# DM2097_Connector_B.net
KiCad netlist of a schematic drawn in Altium Designer
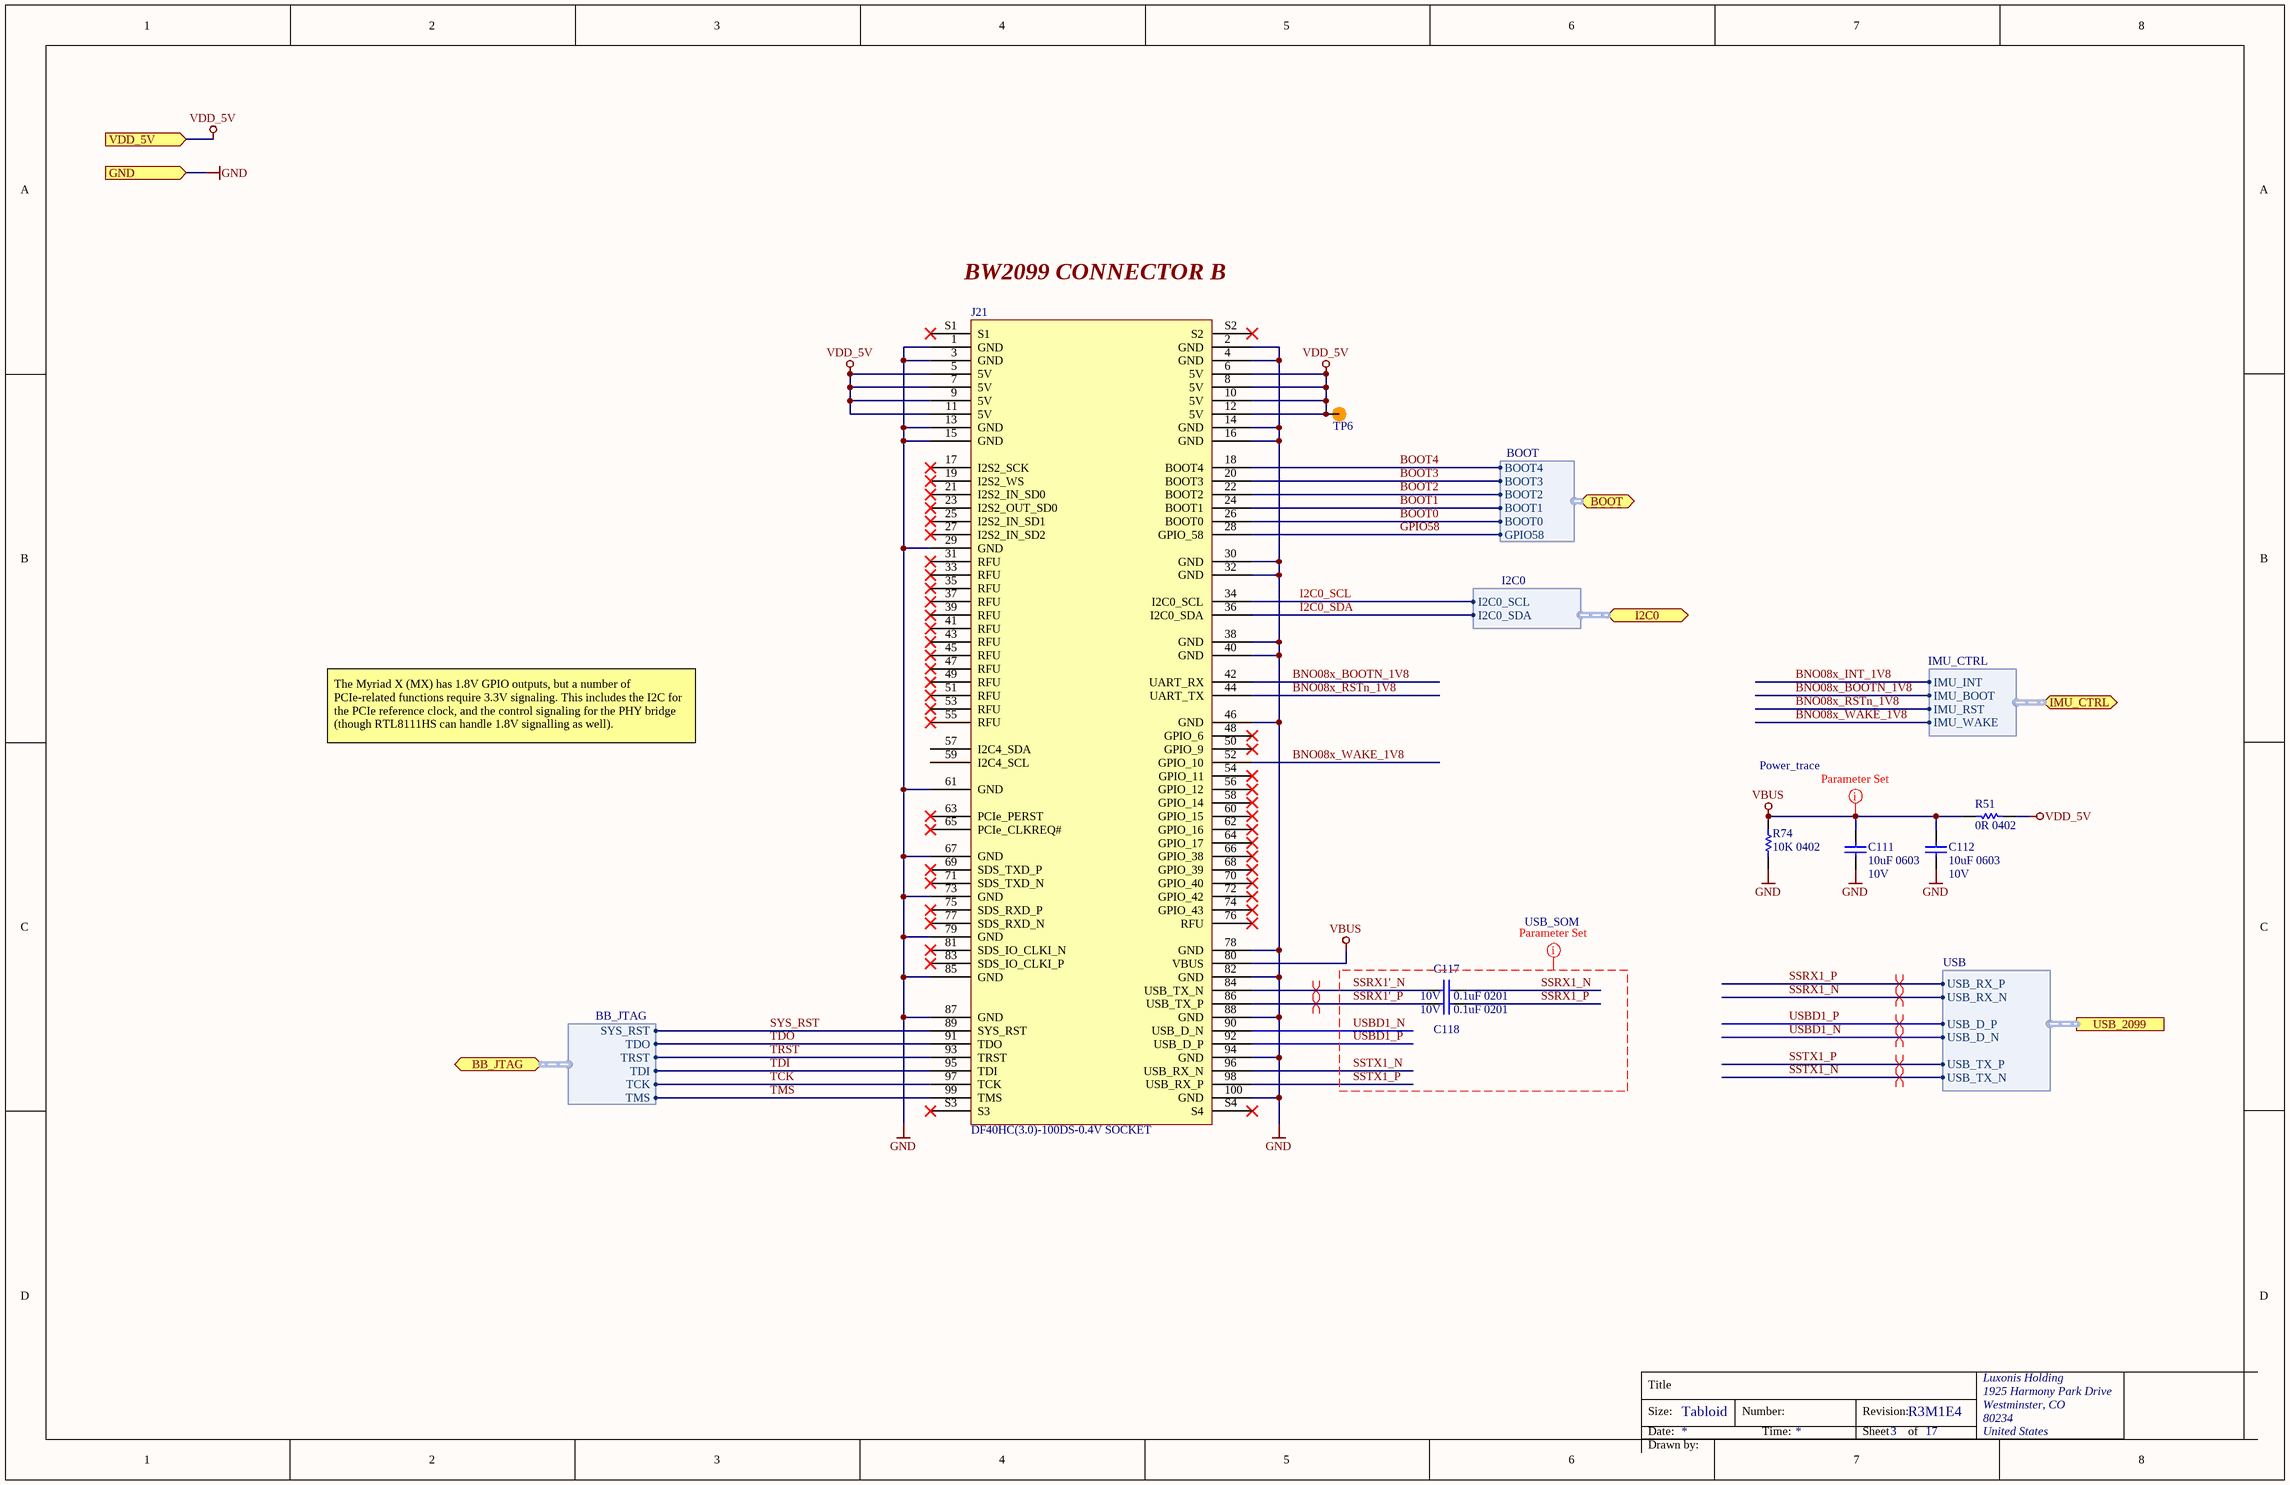
[diagram p0: DM2097_Connector_B.SchDoc]

(export (version "E")
  (design (tool "Eeschema 10.0.6"))
  (components
    (comp (ref "C111")
      (value "10uF 0603")
      (footprint "CAP_Altium_Vault_Generic:CAPC0603(1608)100_N")
      (description "CAP CER 10UF 10V X5R 0603 20%")
      (fields (field (name "TOLERANCE") "20%") (field (name "VOLTAGE RATING") "10V"))
      (libsource (lib "LuxonisMaster") (part "GRM188R61A106ME69D"))
    )
    (comp (ref "C112")
      (value "10uF 0603")
      (footprint "CAP_Altium_Vault_Generic:CAPC0603(1608)100_N")
      (description "CAP CER 10UF 10V X5R 0603 20%")
      (fields (field (name "TOLERANCE") "20%") (field (name "VOLTAGE RATING") "10V"))
      (libsource (lib "LuxonisMaster") (part "GRM188R61A106ME69D"))
    )
    (comp (ref "C117")
      (value "0.1uF 0201")
      (footprint "CAP_Altium_Vault_Generic:CAPC0201(0603)33_L")
      (description "CAP CER 0.1UF 10V X5R 0201")
      (fields (field (name "TOLERANCE") "10%") (field (name "VOLTAGE") "10V"))
      (libsource (lib "LuxonisMaster") (part "GRM033R61A104KE15D"))
    )
    (comp (ref "C118")
      (value "0.1uF 0201")
      (footprint "CAP_Altium_Vault_Generic:CAPC0201(0603)33_L")
      (description "CAP CER 0.1UF 10V X5R 0201")
      (fields (field (name "TOLERANCE") "10%") (field (name "VOLTAGE") "10V"))
      (libsource (lib "LuxonisMaster") (part "GRM033R61A104KE15D"))
    )
    (comp (ref "J21")
      (value "DF40HC(3.0)-100DS-0.4V SOCKET")
      (footprint "DF40HC-3.0-100DS-0.4V_minpad")
      (description "Conn Board to Board RCP 100 POS 0.4mm Solder ST SMD T/R")
      (libsource (lib "LuxonisMaster_OPAL") (part "BW2099_SCKT_Conn_B"))
    )
    (comp (ref "R51")
      (value "0R 0402")
      (footprint "RES_Altium_Vault_Generic:RESC0402(1005)_N")
      (description "RES SMD 0 OHM JUMPER 1/16W 0402")
      (fields (field (name "TOLERANCE") "5%"))
      (libsource (lib "LuxonisMaster") (part "CRCW04020000Z0ED"))
    )
    (comp (ref "R74")
      (value "10K 0402")
      (footprint "RES_Altium_Vault_Generic:RESC0402(1005)_N")
      (fields (field (name "TOLERANCE") "1%"))
      (libsource (lib "LuxonisMaster") (part "RC0402FR-1310KL"))
    )
    (comp (ref "TP6")
      (value "TP100_200_NS")
      (footprint "LuxonisMaster:TP100_200_NS")
      (libsource (lib "LuxonisMaster") (part "TEST_POINT"))
    )
  )
  (nets
    (net (code "6") (name "/BNO08x_BOOTN_1V8") (class "Default")
      (node (ref "J21") (pin "42") (pinfunction "UART_RX_42") (pintype "passive"))
    )
    (net (code "8") (name "/BNO08x_RSTn_1V8") (class "Default")
      (node (ref "J21") (pin "44") (pinfunction "UART_TX_44") (pintype "passive"))
    )
    (net (code "9") (name "/BNO08x_WAKE_1V8") (class "Default")
      (node (ref "J21") (pin "52") (pinfunction "GPIO_10_52") (pintype "passive"))
    )
    (net (code "10") (name "/BOOT0") (class "Default")
      (node (ref "J21") (pin "26") (pinfunction "BOOT0_26") (pintype "passive"))
    )
    (net (code "11") (name "/BOOT1") (class "Default")
      (node (ref "J21") (pin "24") (pinfunction "BOOT1_24") (pintype "passive"))
    )
    (net (code "12") (name "/BOOT2") (class "Default")
      (node (ref "J21") (pin "22") (pinfunction "BOOT2_22") (pintype "passive"))
    )
    (net (code "13") (name "/BOOT3") (class "Default")
      (node (ref "J21") (pin "20") (pinfunction "BOOT3_20") (pintype "passive"))
    )
    (net (code "14") (name "/BOOT4") (class "Default")
      (node (ref "J21") (pin "18") (pinfunction "BOOT4_18") (pintype "passive"))
    )
    (net (code "15") (name "/GPIO58") (class "Default")
      (node (ref "J21") (pin "28") (pinfunction "GPIO_58_28") (pintype "passive"))
    )
    (net (code "16") (name "/I2C0_SCL") (class "Default")
      (node (ref "J21") (pin "34") (pinfunction "I2C0_SCL_34") (pintype "passive"))
    )
    (net (code "17") (name "/I2C0_SDA") (class "Default")
      (node (ref "J21") (pin "36") (pinfunction "I2C0_SDA_36") (pintype "passive"))
    )
    (net (code "18") (name "/SSRX1'_N") (class "Default")
      (node (ref "C117") (pin "1") (pinfunction "1_1") (pintype "passive"))
      (node (ref "J21") (pin "84") (pinfunction "USB_TX_N_84") (pintype "passive"))
    )
    (net (code "19") (name "/SSRX1'_P") (class "Default")
      (node (ref "C118") (pin "1") (pinfunction "1_1") (pintype "passive"))
      (node (ref "J21") (pin "86") (pinfunction "USB_TX_P_86") (pintype "passive"))
    )
    (net (code "20") (name "/SSRX1_N") (class "Default")
      (node (ref "C117") (pin "2") (pinfunction "2_2") (pintype "passive"))
    )
    (net (code "21") (name "/SSRX1_P") (class "Default")
      (node (ref "C118") (pin "2") (pinfunction "2_2") (pintype "passive"))
    )
    (net (code "22") (name "/SSTX1_N") (class "Default")
      (node (ref "J21") (pin "96") (pinfunction "USB_RX_N_96") (pintype "passive"))
    )
    (net (code "23") (name "/SSTX1_P") (class "Default")
      (node (ref "J21") (pin "98") (pinfunction "USB_RX_P_98") (pintype "passive"))
    )
    (net (code "24") (name "/SYS_RST") (class "Default")
      (node (ref "J21") (pin "89") (pinfunction "SYS_RST_89") (pintype "passive"))
    )
    (net (code "25") (name "/TCK") (class "Default")
      (node (ref "J21") (pin "97") (pinfunction "TCK_97") (pintype "passive"))
    )
    (net (code "26") (name "/TDI") (class "Default")
      (node (ref "J21") (pin "95") (pinfunction "TDI_95") (pintype "passive"))
    )
    (net (code "27") (name "/TDO") (class "Default")
      (node (ref "J21") (pin "91") (pinfunction "TDO_91") (pintype "passive"))
    )
    (net (code "28") (name "/TMS") (class "Default")
      (node (ref "J21") (pin "99") (pinfunction "TMS_99") (pintype "passive"))
    )
    (net (code "29") (name "/TRST") (class "Default")
      (node (ref "J21") (pin "93") (pinfunction "TRST_93") (pintype "passive"))
    )
    (net (code "30") (name "/USBD1_N") (class "Default")
      (node (ref "J21") (pin "90") (pinfunction "USB_D_N_90") (pintype "passive"))
    )
    (net (code "31") (name "/USBD1_P") (class "Default")
      (node (ref "J21") (pin "92") (pinfunction "USB_D_P_92") (pintype "passive"))
    )
    (net (code "37") (name "GND") (class "Default")
      (node (ref "C111") (pin "1") (pinfunction "1_1") (pintype "passive"))
      (node (ref "C112") (pin "1") (pinfunction "1_1") (pintype "passive"))
      (node (ref "J21") (pin "1") (pinfunction "GND_1") (pintype "passive"))
      (node (ref "J21") (pin "100") (pinfunction "GND_100") (pintype "passive"))
      (node (ref "J21") (pin "13") (pinfunction "GND_13") (pintype "passive"))
      (node (ref "J21") (pin "14") (pinfunction "GND_14") (pintype "passive"))
      (node (ref "J21") (pin "15") (pinfunction "GND_15") (pintype "passive"))
      (node (ref "J21") (pin "16") (pinfunction "GND_16") (pintype "passive"))
      (node (ref "J21") (pin "2") (pinfunction "GND_2") (pintype "passive"))
      (node (ref "J21") (pin "29") (pinfunction "GND_29") (pintype "passive"))
      (node (ref "J21") (pin "3") (pinfunction "GND_3") (pintype "passive"))
      (node (ref "J21") (pin "30") (pinfunction "GND_30") (pintype "passive"))
      (node (ref "J21") (pin "32") (pinfunction "GND_32") (pintype "passive"))
      (node (ref "J21") (pin "38") (pinfunction "GND_38") (pintype "passive"))
      (node (ref "J21") (pin "4") (pinfunction "GND_4") (pintype "passive"))
      (node (ref "J21") (pin "40") (pinfunction "GND_40") (pintype "passive"))
      (node (ref "J21") (pin "46") (pinfunction "GND_46") (pintype "passive"))
      (node (ref "J21") (pin "61") (pinfunction "GND_61") (pintype "passive"))
      (node (ref "J21") (pin "67") (pinfunction "GND_67") (pintype "passive"))
      (node (ref "J21") (pin "73") (pinfunction "GND_73") (pintype "passive"))
      (node (ref "J21") (pin "78") (pinfunction "GND_78") (pintype "passive"))
      (node (ref "J21") (pin "79") (pinfunction "GND_79") (pintype "passive"))
      (node (ref "J21") (pin "82") (pinfunction "GND_82") (pintype "passive"))
      (node (ref "J21") (pin "85") (pinfunction "GND_85") (pintype "passive"))
      (node (ref "J21") (pin "87") (pinfunction "GND_87") (pintype "passive"))
      (node (ref "J21") (pin "88") (pinfunction "GND_88") (pintype "passive"))
      (node (ref "J21") (pin "94") (pinfunction "GND_94") (pintype "passive"))
      (node (ref "R74") (pin "1") (pinfunction "1_1") (pintype "passive"))
    )
    (net (code "38") (name "VBUS") (class "Default")
      (node (ref "C111") (pin "2") (pinfunction "2_2") (pintype "passive"))
      (node (ref "C112") (pin "2") (pinfunction "2_2") (pintype "passive"))
      (node (ref "J21") (pin "80") (pinfunction "VBUS_80") (pintype "passive"))
      (node (ref "R51") (pin "1") (pinfunction "1_1") (pintype "passive"))
      (node (ref "R74") (pin "2") (pinfunction "2_2") (pintype "passive"))
    )
    (net (code "39") (name "VDD_5V") (class "Default")
      (node (ref "J21") (pin "10") (pinfunction "5V_10") (pintype "passive"))
      (node (ref "J21") (pin "11") (pinfunction "5V_11") (pintype "passive"))
      (node (ref "J21") (pin "12") (pinfunction "5V_12") (pintype "passive"))
      (node (ref "J21") (pin "5") (pinfunction "5V_5") (pintype "passive"))
      (node (ref "J21") (pin "6") (pinfunction "5V_6") (pintype "passive"))
      (node (ref "J21") (pin "7") (pinfunction "5V_7") (pintype "passive"))
      (node (ref "J21") (pin "8") (pinfunction "5V_8") (pintype "passive"))
      (node (ref "J21") (pin "9") (pinfunction "5V_9") (pintype "passive"))
      (node (ref "R51") (pin "2") (pinfunction "2_2") (pintype "passive"))
      (node (ref "TP6") (pin "1") (pintype "passive"))
    )
    (net (code "40") (name "unconnected-(J21-GPIO_6-Pad48)") (class "Default")
      (node (ref "J21") (pin "48") (pinfunction "GPIO_6_48") (pintype "passive+no_connect"))
    )
    (net (code "41") (name "unconnected-(J21-GPIO_9-Pad50)") (class "Default")
      (node (ref "J21") (pin "50") (pinfunction "GPIO_9_50") (pintype "passive+no_connect"))
    )
    (net (code "42") (name "unconnected-(J21-GPIO_11-Pad54)") (class "Default")
      (node (ref "J21") (pin "54") (pinfunction "GPIO_11_54") (pintype "passive+no_connect"))
    )
    (net (code "43") (name "unconnected-(J21-GPIO_12-Pad56)") (class "Default")
      (node (ref "J21") (pin "56") (pinfunction "GPIO_12_56") (pintype "passive+no_connect"))
    )
    (net (code "44") (name "unconnected-(J21-GPIO_14-Pad58)") (class "Default")
      (node (ref "J21") (pin "58") (pinfunction "GPIO_14_58") (pintype "passive+no_connect"))
    )
    (net (code "45") (name "unconnected-(J21-GPIO_15-Pad60)") (class "Default")
      (node (ref "J21") (pin "60") (pinfunction "GPIO_15_60") (pintype "passive+no_connect"))
    )
    (net (code "46") (name "unconnected-(J21-GPIO_16-Pad62)") (class "Default")
      (node (ref "J21") (pin "62") (pinfunction "GPIO_16_62") (pintype "passive+no_connect"))
    )
    (net (code "47") (name "unconnected-(J21-GPIO_17-Pad64)") (class "Default")
      (node (ref "J21") (pin "64") (pinfunction "GPIO_17_64") (pintype "passive+no_connect"))
    )
    (net (code "48") (name "unconnected-(J21-GPIO_38-Pad66)") (class "Default")
      (node (ref "J21") (pin "66") (pinfunction "GPIO_38_66") (pintype "passive+no_connect"))
    )
    (net (code "49") (name "unconnected-(J21-GPIO_39-Pad68)") (class "Default")
      (node (ref "J21") (pin "68") (pinfunction "GPIO_39_68") (pintype "passive+no_connect"))
    )
    (net (code "50") (name "unconnected-(J21-GPIO_40-Pad70)") (class "Default")
      (node (ref "J21") (pin "70") (pinfunction "GPIO_40_70") (pintype "passive+no_connect"))
    )
    (net (code "51") (name "unconnected-(J21-GPIO_42-Pad72)") (class "Default")
      (node (ref "J21") (pin "72") (pinfunction "GPIO_42_72") (pintype "passive+no_connect"))
    )
    (net (code "52") (name "unconnected-(J21-GPIO_43-Pad74)") (class "Default")
      (node (ref "J21") (pin "74") (pinfunction "GPIO_43_74") (pintype "passive+no_connect"))
    )
    (net (code "53") (name "unconnected-(J21-I2C4_SCL-Pad59)") (class "Default")
      (node (ref "J21") (pin "59") (pinfunction "I2C4_SCL_59") (pintype "passive"))
    )
    (net (code "54") (name "unconnected-(J21-I2C4_SDA-Pad57)") (class "Default")
      (node (ref "J21") (pin "57") (pinfunction "I2C4_SDA_57") (pintype "passive"))
    )
    (net (code "55") (name "unconnected-(J21-I2S2_IN_SD0-Pad21)") (class "Default")
      (node (ref "J21") (pin "21") (pinfunction "I2S2_IN_SD0_21") (pintype "passive+no_connect"))
    )
    (net (code "56") (name "unconnected-(J21-I2S2_IN_SD1-Pad25)") (class "Default")
      (node (ref "J21") (pin "25") (pinfunction "I2S2_IN_SD1_25") (pintype "passive+no_connect"))
    )
    (net (code "57") (name "unconnected-(J21-I2S2_IN_SD2-Pad27)") (class "Default")
      (node (ref "J21") (pin "27") (pinfunction "I2S2_IN_SD2_27") (pintype "passive+no_connect"))
    )
    (net (code "58") (name "unconnected-(J21-I2S2_OUT_SD0-Pad23)") (class "Default")
      (node (ref "J21") (pin "23") (pinfunction "I2S2_OUT_SD0_23") (pintype "passive+no_connect"))
    )
    (net (code "59") (name "unconnected-(J21-I2S2_SCK-Pad17)") (class "Default")
      (node (ref "J21") (pin "17") (pinfunction "I2S2_SCK_17") (pintype "passive+no_connect"))
    )
    (net (code "60") (name "unconnected-(J21-I2S2_WS-Pad19)") (class "Default")
      (node (ref "J21") (pin "19") (pinfunction "I2S2_WS_19") (pintype "passive+no_connect"))
    )
    (net (code "61") (name "unconnected-(J21-PCIe_CLKREQ#-Pad65)") (class "Default")
      (node (ref "J21") (pin "65") (pinfunction "PCIe_CLKREQ#_65") (pintype "passive+no_connect"))
    )
    (net (code "62") (name "unconnected-(J21-PCIe_PERST-Pad63)") (class "Default")
      (node (ref "J21") (pin "63") (pinfunction "PCIe_PERST_63") (pintype "passive+no_connect"))
    )
    (net (code "63") (name "unconnected-(J21-PadS1)") (class "Default")
      (node (ref "J21") (pin "S1") (pinfunction "S1_S1") (pintype "passive+no_connect"))
    )
    (net (code "64") (name "unconnected-(J21-PadS2)") (class "Default")
      (node (ref "J21") (pin "S2") (pinfunction "S2_S2") (pintype "passive+no_connect"))
    )
    (net (code "65") (name "unconnected-(J21-PadS3)") (class "Default")
      (node (ref "J21") (pin "S3") (pinfunction "S3_S3") (pintype "passive+no_connect"))
    )
    (net (code "66") (name "unconnected-(J21-PadS4)") (class "Default")
      (node (ref "J21") (pin "S4") (pinfunction "S4_S4") (pintype "passive+no_connect"))
    )
    (net (code "67") (name "unconnected-(J21-RFU-Pad31)") (class "Default")
      (node (ref "J21") (pin "31") (pinfunction "RFU_31") (pintype "passive+no_connect"))
    )
    (net (code "68") (name "unconnected-(J21-RFU-Pad33)") (class "Default")
      (node (ref "J21") (pin "33") (pinfunction "RFU_33") (pintype "passive+no_connect"))
    )
    (net (code "69") (name "unconnected-(J21-RFU-Pad35)") (class "Default")
      (node (ref "J21") (pin "35") (pinfunction "RFU_35") (pintype "passive+no_connect"))
    )
    (net (code "70") (name "unconnected-(J21-RFU-Pad37)") (class "Default")
      (node (ref "J21") (pin "37") (pinfunction "RFU_37") (pintype "passive+no_connect"))
    )
    (net (code "71") (name "unconnected-(J21-RFU-Pad39)") (class "Default")
      (node (ref "J21") (pin "39") (pinfunction "RFU_39") (pintype "passive+no_connect"))
    )
    (net (code "72") (name "unconnected-(J21-RFU-Pad41)") (class "Default")
      (node (ref "J21") (pin "41") (pinfunction "RFU_41") (pintype "passive+no_connect"))
    )
    (net (code "73") (name "unconnected-(J21-RFU-Pad43)") (class "Default")
      (node (ref "J21") (pin "43") (pinfunction "RFU_43") (pintype "passive+no_connect"))
    )
    (net (code "74") (name "unconnected-(J21-RFU-Pad45)") (class "Default")
      (node (ref "J21") (pin "45") (pinfunction "RFU_45") (pintype "passive+no_connect"))
    )
    (net (code "75") (name "unconnected-(J21-RFU-Pad47)") (class "Default")
      (node (ref "J21") (pin "47") (pinfunction "RFU_47") (pintype "passive+no_connect"))
    )
    (net (code "76") (name "unconnected-(J21-RFU-Pad49)") (class "Default")
      (node (ref "J21") (pin "49") (pinfunction "RFU_49") (pintype "passive+no_connect"))
    )
    (net (code "77") (name "unconnected-(J21-RFU-Pad51)") (class "Default")
      (node (ref "J21") (pin "51") (pinfunction "RFU_51") (pintype "passive+no_connect"))
    )
    (net (code "78") (name "unconnected-(J21-RFU-Pad53)") (class "Default")
      (node (ref "J21") (pin "53") (pinfunction "RFU_53") (pintype "passive+no_connect"))
    )
    (net (code "79") (name "unconnected-(J21-RFU-Pad55)") (class "Default")
      (node (ref "J21") (pin "55") (pinfunction "RFU_55") (pintype "passive+no_connect"))
    )
    (net (code "80") (name "unconnected-(J21-RFU-Pad76)") (class "Default")
      (node (ref "J21") (pin "76") (pinfunction "RFU_76") (pintype "passive+no_connect"))
    )
    (net (code "81") (name "unconnected-(J21-SDS_IO_CLKI_N-Pad81)") (class "Default")
      (node (ref "J21") (pin "81") (pinfunction "SDS_IO_CLKI_N_81") (pintype "passive+no_connect"))
    )
    (net (code "82") (name "unconnected-(J21-SDS_IO_CLKI_P-Pad83)") (class "Default")
      (node (ref "J21") (pin "83") (pinfunction "SDS_IO_CLKI_P_83") (pintype "passive+no_connect"))
    )
    (net (code "83") (name "unconnected-(J21-SDS_RXD_N-Pad77)") (class "Default")
      (node (ref "J21") (pin "77") (pinfunction "SDS_RXD_N_77") (pintype "passive+no_connect"))
    )
    (net (code "84") (name "unconnected-(J21-SDS_RXD_P-Pad75)") (class "Default")
      (node (ref "J21") (pin "75") (pinfunction "SDS_RXD_P_75") (pintype "passive+no_connect"))
    )
    (net (code "85") (name "unconnected-(J21-SDS_TXD_N-Pad71)") (class "Default")
      (node (ref "J21") (pin "71") (pinfunction "SDS_TXD_N_71") (pintype "passive+no_connect"))
    )
    (net (code "86") (name "unconnected-(J21-SDS_TXD_P-Pad69)") (class "Default")
      (node (ref "J21") (pin "69") (pinfunction "SDS_TXD_P_69") (pintype "passive+no_connect"))
    )
  )
)
